# JTAG.net
KiCad netlist of a schematic drawn in Altium Designer
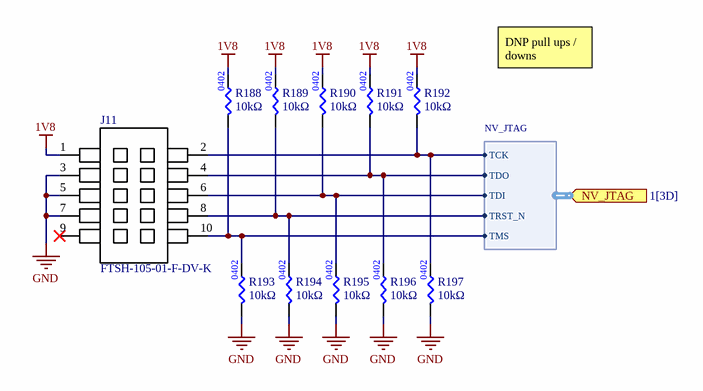
[diagram p0: JTAG.SchDoc]

(export (version "E")
  (design (tool "Eeschema 10.0.6"))
  (components
    (comp (ref "J11")
      (value "CON_PROGRAMMING")
      (footprint "FTSH-105-01-F-DV-K-P-TR")
      (description "CONN HEADER SMD 10POS 1.27MM")
      (fields (field (name "MANUFACTURER PART NUMBER 1") "FTSH-105-01-F-DV-K"))
      (libsource (lib "UWRT_Schematic_Library_2020") (part "CON_PROGRAMMING"))
    )
    (comp (ref "R188")
      (value "RES_10kΩ_0402_1%")
      (footprint "RES0402")
      (description "RES 10K OHM 1% 1/16W 0402")
      (fields (field (name "TOLERANCE") "1%") (field (name "RESISTANCE") "10kΩ"))
      (libsource (lib "UWRT_Schematic_Library_2020") (part "RES_10kΩ_0402_1%"))
    )
    (comp (ref "R189")
      (value "RES_10kΩ_0402_1%")
      (footprint "RES0402")
      (description "RES 10K OHM 1% 1/16W 0402")
      (fields (field (name "TOLERANCE") "1%") (field (name "RESISTANCE") "10kΩ"))
      (libsource (lib "UWRT_Schematic_Library_2020") (part "RES_10kΩ_0402_1%"))
    )
    (comp (ref "R190")
      (value "RES_10kΩ_0402_1%")
      (footprint "RES0402")
      (description "RES 10K OHM 1% 1/16W 0402")
      (fields (field (name "TOLERANCE") "1%") (field (name "RESISTANCE") "10kΩ"))
      (libsource (lib "UWRT_Schematic_Library_2020") (part "RES_10kΩ_0402_1%"))
    )
    (comp (ref "R191")
      (value "RES_10kΩ_0402_1%")
      (footprint "RES0402")
      (description "RES 10K OHM 1% 1/16W 0402")
      (fields (field (name "TOLERANCE") "1%") (field (name "RESISTANCE") "10kΩ"))
      (libsource (lib "UWRT_Schematic_Library_2020") (part "RES_10kΩ_0402_1%"))
    )
    (comp (ref "R192")
      (value "RES_10kΩ_0402_1%")
      (footprint "RES0402")
      (description "RES 10K OHM 1% 1/16W 0402")
      (fields (field (name "TOLERANCE") "1%") (field (name "RESISTANCE") "10kΩ"))
      (libsource (lib "UWRT_Schematic_Library_2020") (part "RES_10kΩ_0402_1%"))
    )
    (comp (ref "R193")
      (value "RES_10kΩ_0402_1%")
      (footprint "RES0402")
      (description "RES 10K OHM 1% 1/16W 0402")
      (fields (field (name "TOLERANCE") "1%") (field (name "RESISTANCE") "10kΩ"))
      (libsource (lib "UWRT_Schematic_Library_2020") (part "RES_10kΩ_0402_1%"))
    )
    (comp (ref "R194")
      (value "RES_10kΩ_0402_1%")
      (footprint "RES0402")
      (description "RES 10K OHM 1% 1/16W 0402")
      (fields (field (name "TOLERANCE") "1%") (field (name "RESISTANCE") "10kΩ"))
      (libsource (lib "UWRT_Schematic_Library_2020") (part "RES_10kΩ_0402_1%"))
    )
    (comp (ref "R195")
      (value "RES_10kΩ_0402_1%")
      (footprint "RES0402")
      (description "RES 10K OHM 1% 1/16W 0402")
      (fields (field (name "TOLERANCE") "1%") (field (name "RESISTANCE") "10kΩ"))
      (libsource (lib "UWRT_Schematic_Library_2020") (part "RES_10kΩ_0402_1%"))
    )
    (comp (ref "R196")
      (value "RES_10kΩ_0402_1%")
      (footprint "RES0402")
      (description "RES 10K OHM 1% 1/16W 0402")
      (fields (field (name "TOLERANCE") "1%") (field (name "RESISTANCE") "10kΩ"))
      (libsource (lib "UWRT_Schematic_Library_2020") (part "RES_10kΩ_0402_1%"))
    )
    (comp (ref "R197")
      (value "RES_10kΩ_0402_1%")
      (footprint "RES0402")
      (description "RES 10K OHM 1% 1/16W 0402")
      (fields (field (name "TOLERANCE") "1%") (field (name "RESISTANCE") "10kΩ"))
      (libsource (lib "UWRT_Schematic_Library_2020") (part "RES_10kΩ_0402_1%"))
    )
  )
  (nets
    (net (code "3") (name "1V8") (class "Default")
      (node (ref "J11") (pin "1") (pinfunction "1_1") (pintype "passive"))
      (node (ref "R188") (pin "2") (pinfunction "2_2") (pintype "passive"))
      (node (ref "R189") (pin "2") (pinfunction "2_2") (pintype "passive"))
      (node (ref "R190") (pin "2") (pinfunction "2_2") (pintype "passive"))
      (node (ref "R191") (pin "2") (pinfunction "2_2") (pintype "passive"))
      (node (ref "R192") (pin "2") (pinfunction "2_2") (pintype "passive"))
    )
    (net (code "4") (name "GND") (class "Default")
      (node (ref "J11") (pin "3") (pinfunction "3_3") (pintype "passive"))
      (node (ref "J11") (pin "5") (pinfunction "5_5") (pintype "passive"))
      (node (ref "J11") (pin "7") (pinfunction "7_7") (pintype "passive"))
      (node (ref "R193") (pin "1") (pinfunction "1_1") (pintype "passive"))
      (node (ref "R194") (pin "1") (pinfunction "1_1") (pintype "passive"))
      (node (ref "R195") (pin "1") (pinfunction "1_1") (pintype "passive"))
      (node (ref "R196") (pin "1") (pinfunction "1_1") (pintype "passive"))
      (node (ref "R197") (pin "1") (pinfunction "1_1") (pintype "passive"))
    )
    (net (code "5") (name "Net-(J11-Pad2)") (class "Default")
      (node (ref "J11") (pin "2") (pinfunction "2_2") (pintype "passive"))
      (node (ref "R192") (pin "1") (pinfunction "1_1") (pintype "passive"))
      (node (ref "R197") (pin "2") (pinfunction "2_2") (pintype "passive"))
    )
    (net (code "6") (name "Net-(J11-Pad4)") (class "Default")
      (node (ref "J11") (pin "4") (pinfunction "4_4") (pintype "passive"))
      (node (ref "R191") (pin "1") (pinfunction "1_1") (pintype "passive"))
      (node (ref "R196") (pin "2") (pinfunction "2_2") (pintype "passive"))
    )
    (net (code "7") (name "Net-(J11-Pad6)") (class "Default")
      (node (ref "J11") (pin "6") (pinfunction "6_6") (pintype "passive"))
      (node (ref "R190") (pin "1") (pinfunction "1_1") (pintype "passive"))
      (node (ref "R195") (pin "2") (pinfunction "2_2") (pintype "passive"))
    )
    (net (code "8") (name "Net-(J11-Pad8)") (class "Default")
      (node (ref "J11") (pin "8") (pinfunction "8_8") (pintype "passive"))
      (node (ref "R189") (pin "1") (pinfunction "1_1") (pintype "passive"))
      (node (ref "R194") (pin "2") (pinfunction "2_2") (pintype "passive"))
    )
    (net (code "9") (name "Net-(J11-Pad10)") (class "Default")
      (node (ref "J11") (pin "10") (pinfunction "10_10") (pintype "passive"))
      (node (ref "R188") (pin "1") (pinfunction "1_1") (pintype "passive"))
      (node (ref "R193") (pin "2") (pinfunction "2_2") (pintype "passive"))
    )
    (net (code "10") (name "unconnected-(J11-Pad9)") (class "Default")
      (node (ref "J11") (pin "9") (pinfunction "9_9") (pintype "passive+no_connect"))
    )
  )
)
